# Single_Turnoutv0_2.net
KiCad netlist of a schematic drawn in EAGLE
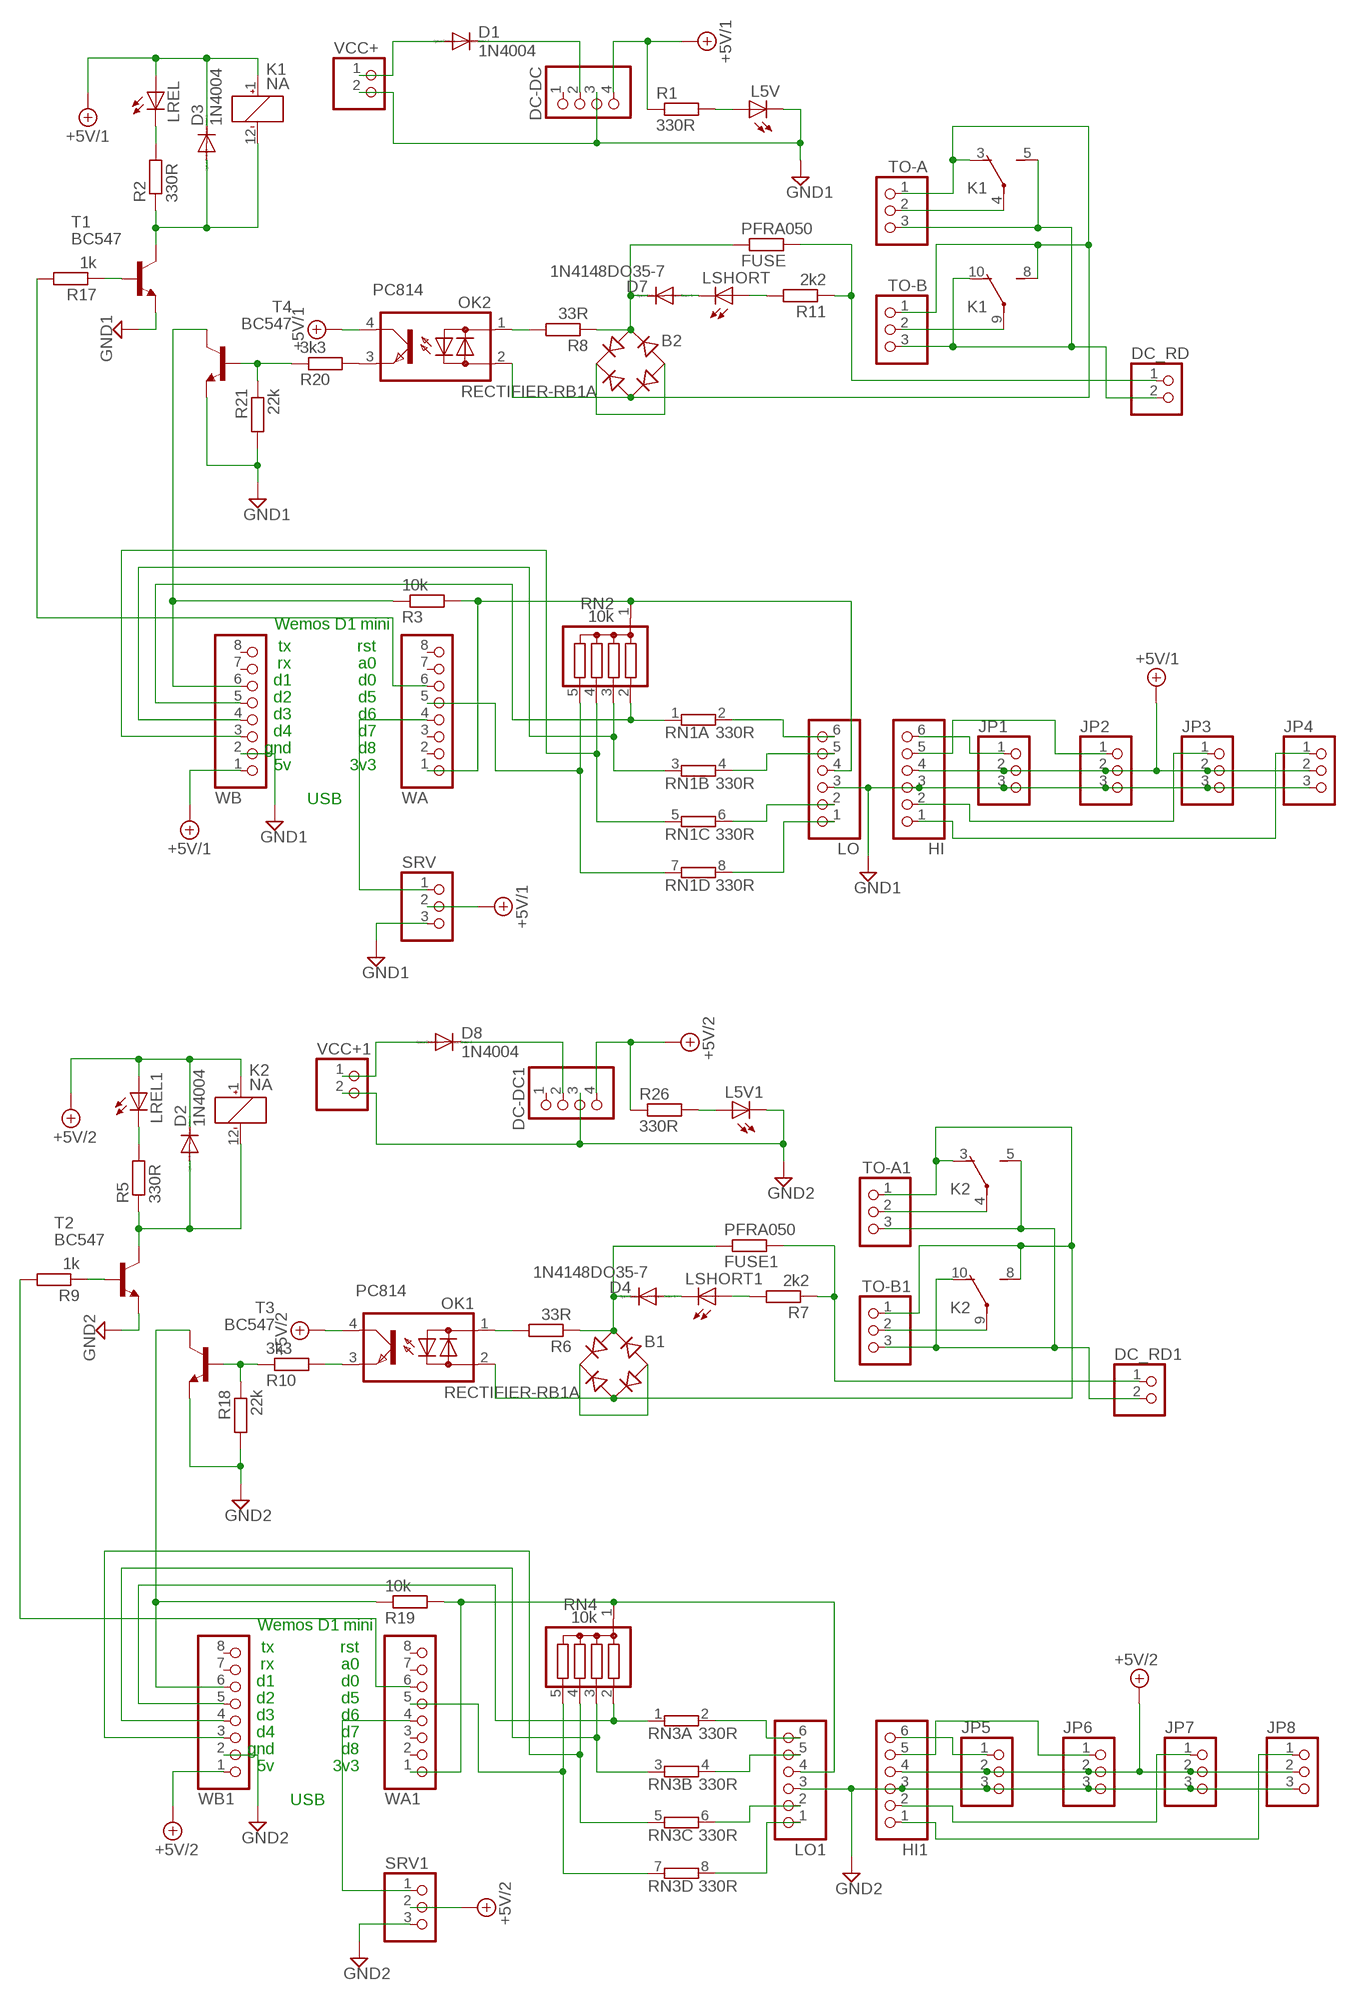
[diagram p0: schematic, sheet 1]

(export (version "E")
  (design (tool "Eeschema 10.0.6"))
  (components
    (comp (ref "B1")
      (value "RECTIFIER-RB1A")
      (footprint "eagle-import:RB1A")
      (libsource (lib "eagle-import") (part "RECTIFIER-RB1A"))
    )
    (comp (ref "B2")
      (value "RECTIFIER-RB1A")
      (footprint "eagle-import:RB1A")
      (libsource (lib "eagle-import") (part "RECTIFIER-RB1A"))
    )
    (comp (ref "D1")
      (value "1N4004")
      (footprint "eagle-import:DO41-10")
      (libsource (lib "eagle-import") (part "1N4004"))
    )
    (comp (ref "D2")
      (value "1N4004")
      (footprint "eagle-import:DO41-10")
      (libsource (lib "eagle-import") (part "1N4004"))
    )
    (comp (ref "D3")
      (value "1N4004")
      (footprint "eagle-import:DO41-10")
      (libsource (lib "eagle-import") (part "1N4004"))
    )
    (comp (ref "D4")
      (value "1N4148DO35-7")
      (footprint "eagle-import:DO35-7")
      (libsource (lib "eagle-import") (part "1N4148DO35-7"))
    )
    (comp (ref "D7")
      (value "1N4148DO35-7")
      (footprint "eagle-import:DO35-7")
      (libsource (lib "eagle-import") (part "1N4148DO35-7"))
    )
    (comp (ref "D8")
      (value "1N4004")
      (footprint "eagle-import:DO41-10")
      (libsource (lib "eagle-import") (part "1N4004"))
    )
    (comp (ref "DC-DC")
      (value "PINHD-1X4")
      (footprint "eagle-import:1X04")
      (libsource (lib "eagle-import") (part "PINHD-1X4"))
    )
    (comp (ref "DC-DC1")
      (value "PINHD-1X4")
      (footprint "eagle-import:1X04")
      (libsource (lib "eagle-import") (part "PINHD-1X4"))
    )
    (comp (ref "DC_RD")
      (value "PINHD-1X2")
      (footprint "eagle-import:1X02")
      (libsource (lib "eagle-import") (part "PINHD-1X2"))
    )
    (comp (ref "DC_RD1")
      (value "PINHD-1X2")
      (footprint "eagle-import:1X02")
      (libsource (lib "eagle-import") (part "PINHD-1X2"))
    )
    (comp (ref "FUSE")
      (value "PFRA050")
      (footprint "eagle-import:0414V")
      (libsource (lib "eagle-import") (part "R-EU_0414/5V"))
    )
    (comp (ref "FUSE1")
      (value "PFRA050")
      (footprint "eagle-import:0414V")
      (libsource (lib "eagle-import") (part "R-EU_0414/5V"))
    )
    (comp (ref "HI")
      (value "PINHD-1X6")
      (footprint "eagle-import:1X06")
      (libsource (lib "eagle-import") (part "PINHD-1X6"))
    )
    (comp (ref "HI1")
      (value "PINHD-1X6")
      (footprint "eagle-import:1X06")
      (libsource (lib "eagle-import") (part "PINHD-1X6"))
    )
    (comp (ref "JP1")
      (value "PINHD-1X3")
      (footprint "eagle-import:1X03")
      (libsource (lib "eagle-import") (part "pinhead_325_PINHD-1X3"))
    )
    (comp (ref "JP2")
      (value "PINHD-1X3")
      (footprint "eagle-import:1X03")
      (libsource (lib "eagle-import") (part "pinhead_325_PINHD-1X3"))
    )
    (comp (ref "JP3")
      (value "PINHD-1X3")
      (footprint "eagle-import:1X03")
      (libsource (lib "eagle-import") (part "pinhead_325_PINHD-1X3"))
    )
    (comp (ref "JP4")
      (value "PINHD-1X3")
      (footprint "eagle-import:1X03")
      (libsource (lib "eagle-import") (part "pinhead_325_PINHD-1X3"))
    )
    (comp (ref "JP5")
      (value "PINHD-1X3")
      (footprint "eagle-import:1X03")
      (libsource (lib "eagle-import") (part "pinhead_325_PINHD-1X3"))
    )
    (comp (ref "JP6")
      (value "PINHD-1X3")
      (footprint "eagle-import:1X03")
      (libsource (lib "eagle-import") (part "pinhead_325_PINHD-1X3"))
    )
    (comp (ref "JP7")
      (value "PINHD-1X3")
      (footprint "eagle-import:1X03")
      (libsource (lib "eagle-import") (part "pinhead_325_PINHD-1X3"))
    )
    (comp (ref "JP8")
      (value "PINHD-1X3")
      (footprint "eagle-import:1X03")
      (libsource (lib "eagle-import") (part "pinhead_325_PINHD-1X3"))
    )
    (comp (ref "K1") (value "NA") (footprint "eagle-import:NA") (libsource (lib "eagle-import") (part "NA")))
    (comp (ref "K2") (value "NA") (footprint "eagle-import:NA") (libsource (lib "eagle-import") (part "NA")))
    (comp (ref "L5V")
      (value "LED3MM")
      (footprint "eagle-import:LED3MM")
      (libsource (lib "eagle-import") (part "LED3MM"))
    )
    (comp (ref "L5V1")
      (value "LED3MM")
      (footprint "eagle-import:LED3MM")
      (libsource (lib "eagle-import") (part "LED3MM"))
    )
    (comp (ref "LO")
      (value "PINHD-1X6")
      (footprint "eagle-import:1X06")
      (libsource (lib "eagle-import") (part "PINHD-1X6"))
    )
    (comp (ref "LO1")
      (value "PINHD-1X6")
      (footprint "eagle-import:1X06")
      (libsource (lib "eagle-import") (part "PINHD-1X6"))
    )
    (comp (ref "LREL")
      (value "LED3MM")
      (footprint "eagle-import:LED3MM")
      (libsource (lib "eagle-import") (part "LED3MM"))
    )
    (comp (ref "LREL1")
      (value "LED3MM")
      (footprint "eagle-import:LED3MM")
      (libsource (lib "eagle-import") (part "LED3MM"))
    )
    (comp (ref "LSHORT")
      (value "LED3MM")
      (footprint "eagle-import:LED3MM")
      (libsource (lib "eagle-import") (part "LED3MM"))
    )
    (comp (ref "LSHORT1")
      (value "LED3MM")
      (footprint "eagle-import:LED3MM")
      (libsource (lib "eagle-import") (part "LED3MM"))
    )
    (comp (ref "OK1")
      (value "PC814")
      (footprint "eagle-import:DIL04")
      (libsource (lib "eagle-import") (part "PC814"))
    )
    (comp (ref "OK2")
      (value "PC814")
      (footprint "eagle-import:DIL04")
      (libsource (lib "eagle-import") (part "PC814"))
    )
    (comp (ref "R1")
      (value "330R")
      (footprint "eagle-import:0207_7")
      (libsource (lib "eagle-import") (part "resistor_348_R-EU_0207/7"))
    )
    (comp (ref "R2")
      (value "330R")
      (footprint "eagle-import:0207_7")
      (libsource (lib "eagle-import") (part "resistor_348_R-EU_0207/7"))
    )
    (comp (ref "R3")
      (value "10k")
      (footprint "eagle-import:0207_7")
      (libsource (lib "eagle-import") (part "resistor_348_R-EU_0207/7"))
    )
    (comp (ref "R5")
      (value "330R")
      (footprint "eagle-import:0207_7")
      (libsource (lib "eagle-import") (part "resistor_348_R-EU_0207/7"))
    )
    (comp (ref "R6")
      (value "33R")
      (footprint "eagle-import:0207_7")
      (libsource (lib "eagle-import") (part "resistor_348_R-EU_0207/7"))
    )
    (comp (ref "R7")
      (value "2k2")
      (footprint "eagle-import:0207_7")
      (libsource (lib "eagle-import") (part "resistor_348_R-EU_0207/7"))
    )
    (comp (ref "R8")
      (value "33R")
      (footprint "eagle-import:0207_7")
      (libsource (lib "eagle-import") (part "resistor_348_R-EU_0207/7"))
    )
    (comp (ref "R9")
      (value "1k")
      (footprint "eagle-import:0207_7")
      (libsource (lib "eagle-import") (part "resistor_348_R-EU_0207/7"))
    )
    (comp (ref "R10")
      (value "3k3")
      (footprint "eagle-import:0207_7")
      (libsource (lib "eagle-import") (part "resistor_348_R-EU_0207/7"))
    )
    (comp (ref "R11")
      (value "2k2")
      (footprint "eagle-import:0207_7")
      (libsource (lib "eagle-import") (part "resistor_348_R-EU_0207/7"))
    )
    (comp (ref "R17")
      (value "1k")
      (footprint "eagle-import:0207_7")
      (libsource (lib "eagle-import") (part "resistor_348_R-EU_0207/7"))
    )
    (comp (ref "R18")
      (value "22k")
      (footprint "eagle-import:0207_7")
      (libsource (lib "eagle-import") (part "resistor_348_R-EU_0207/7"))
    )
    (comp (ref "R19")
      (value "10k")
      (footprint "eagle-import:0207_7")
      (libsource (lib "eagle-import") (part "resistor_348_R-EU_0207/7"))
    )
    (comp (ref "R20")
      (value "3k3")
      (footprint "eagle-import:0207_7")
      (libsource (lib "eagle-import") (part "resistor_348_R-EU_0207/7"))
    )
    (comp (ref "R21")
      (value "22k")
      (footprint "eagle-import:0207_7")
      (libsource (lib "eagle-import") (part "resistor_348_R-EU_0207/7"))
    )
    (comp (ref "R26")
      (value "330R")
      (footprint "eagle-import:0207_7")
      (libsource (lib "eagle-import") (part "resistor_348_R-EU_0207/7"))
    )
    (comp (ref "RN1")
      (value "330R")
      (footprint "eagle-import:SIL8")
      (libsource (lib "eagle-import") (part "E4R"))
    )
    (comp (ref "RN2")
      (value "10k")
      (footprint "eagle-import:SIL5")
      (libsource (lib "eagle-import") (part "G04R"))
    )
    (comp (ref "RN3")
      (value "330R")
      (footprint "eagle-import:SIL8")
      (libsource (lib "eagle-import") (part "E4R"))
    )
    (comp (ref "RN4")
      (value "10k")
      (footprint "eagle-import:SIL5")
      (libsource (lib "eagle-import") (part "G04R"))
    )
    (comp (ref "SRV")
      (value "PINHD-1X3")
      (footprint "eagle-import:1X03")
      (libsource (lib "eagle-import") (part "PINHD-1X3"))
    )
    (comp (ref "SRV1")
      (value "PINHD-1X3")
      (footprint "eagle-import:1X03")
      (libsource (lib "eagle-import") (part "PINHD-1X3"))
    )
    (comp (ref "T1")
      (value "BC547")
      (footprint "eagle-import:TO92")
      (libsource (lib "eagle-import") (part "BC547"))
    )
    (comp (ref "T2")
      (value "BC547")
      (footprint "eagle-import:TO92")
      (libsource (lib "eagle-import") (part "BC547"))
    )
    (comp (ref "T3")
      (value "BC547")
      (footprint "eagle-import:TO92")
      (libsource (lib "eagle-import") (part "BC547"))
    )
    (comp (ref "T4")
      (value "BC547")
      (footprint "eagle-import:TO92")
      (libsource (lib "eagle-import") (part "BC547"))
    )
    (comp (ref "TO-A")
      (value "PINHD-1X3")
      (footprint "eagle-import:1X03")
      (libsource (lib "eagle-import") (part "PINHD-1X3"))
    )
    (comp (ref "TO-A1")
      (value "PINHD-1X3")
      (footprint "eagle-import:1X03")
      (libsource (lib "eagle-import") (part "PINHD-1X3"))
    )
    (comp (ref "TO-B")
      (value "PINHD-1X3")
      (footprint "eagle-import:1X03")
      (libsource (lib "eagle-import") (part "PINHD-1X3"))
    )
    (comp (ref "TO-B1")
      (value "PINHD-1X3")
      (footprint "eagle-import:1X03")
      (libsource (lib "eagle-import") (part "PINHD-1X3"))
    )
    (comp (ref "VCC+")
      (value "PINHD-1X2")
      (footprint "eagle-import:1X02")
      (libsource (lib "eagle-import") (part "PINHD-1X2"))
    )
    (comp (ref "VCC+1")
      (value "PINHD-1X2")
      (footprint "eagle-import:1X02")
      (libsource (lib "eagle-import") (part "PINHD-1X2"))
    )
    (comp (ref "WA")
      (value "PINHD-1X8")
      (footprint "eagle-import:1X08")
      (libsource (lib "eagle-import") (part "PINHD-1X8"))
    )
    (comp (ref "WA1")
      (value "PINHD-1X8")
      (footprint "eagle-import:1X08")
      (libsource (lib "eagle-import") (part "PINHD-1X8"))
    )
    (comp (ref "WB")
      (value "PINHD-1X8")
      (footprint "eagle-import:1X08")
      (libsource (lib "eagle-import") (part "PINHD-1X8"))
    )
    (comp (ref "WB1")
      (value "PINHD-1X8")
      (footprint "eagle-import:1X08")
      (libsource (lib "eagle-import") (part "PINHD-1X8"))
    )
  )
  (nets
    (net (code "1") (name "+5V{slash}1") (class "Default")
      (node (ref "D3") (pin "C") (pinfunction "C_C") (pintype "passive"))
      (node (ref "DC-DC") (pin "4") (pinfunction "4_4") (pintype "passive"))
      (node (ref "HI") (pin "4") (pinfunction "4_4") (pintype "passive"))
      (node (ref "JP1") (pin "2") (pinfunction "2_2") (pintype "passive"))
      (node (ref "JP2") (pin "2") (pinfunction "2_2") (pintype "passive"))
      (node (ref "JP3") (pin "2") (pinfunction "2_2") (pintype "passive"))
      (node (ref "JP4") (pin "2") (pinfunction "2_2") (pintype "passive"))
      (node (ref "K1") (pin "1") (pinfunction "+_1") (pintype "passive"))
      (node (ref "LREL") (pin "A") (pinfunction "A_A") (pintype "passive"))
      (node (ref "OK2") (pin "4") (pinfunction "C_4") (pintype "passive"))
      (node (ref "R1") (pin "1") (pinfunction "1_1") (pintype "passive"))
      (node (ref "SRV") (pin "2") (pinfunction "2_2") (pintype "passive"))
      (node (ref "WB") (pin "1") (pinfunction "1_1") (pintype "passive"))
    )
    (net (code "2") (name "+5V{slash}2") (class "Default")
      (node (ref "D2") (pin "C") (pinfunction "C_C") (pintype "passive"))
      (node (ref "DC-DC1") (pin "4") (pinfunction "4_4") (pintype "passive"))
      (node (ref "HI1") (pin "4") (pinfunction "4_4") (pintype "passive"))
      (node (ref "JP5") (pin "2") (pinfunction "2_2") (pintype "passive"))
      (node (ref "JP6") (pin "2") (pinfunction "2_2") (pintype "passive"))
      (node (ref "JP7") (pin "2") (pinfunction "2_2") (pintype "passive"))
      (node (ref "JP8") (pin "2") (pinfunction "2_2") (pintype "passive"))
      (node (ref "K2") (pin "1") (pinfunction "+_1") (pintype "passive"))
      (node (ref "LREL1") (pin "A") (pinfunction "A_A") (pintype "passive"))
      (node (ref "OK1") (pin "4") (pinfunction "C_4") (pintype "passive"))
      (node (ref "R26") (pin "1") (pinfunction "1_1") (pintype "passive"))
      (node (ref "SRV1") (pin "2") (pinfunction "2_2") (pintype "passive"))
      (node (ref "WB1") (pin "1") (pinfunction "1_1") (pintype "passive"))
    )
    (net (code "3") (name "GND1") (class "Default")
      (node (ref "DC-DC") (pin "3") (pinfunction "3_3") (pintype "passive"))
      (node (ref "HI") (pin "3") (pinfunction "3_3") (pintype "passive"))
      (node (ref "JP1") (pin "3") (pinfunction "3_3") (pintype "passive"))
      (node (ref "JP2") (pin "3") (pinfunction "3_3") (pintype "passive"))
      (node (ref "JP3") (pin "3") (pinfunction "3_3") (pintype "passive"))
      (node (ref "JP4") (pin "3") (pinfunction "3_3") (pintype "passive"))
      (node (ref "L5V") (pin "K") (pinfunction "C_K") (pintype "passive"))
      (node (ref "LO") (pin "3") (pinfunction "3_3") (pintype "passive"))
      (node (ref "R21") (pin "2") (pinfunction "2_2") (pintype "passive"))
      (node (ref "SRV") (pin "3") (pinfunction "3_3") (pintype "passive"))
      (node (ref "T1") (pin "1") (pinfunction "E_1") (pintype "passive"))
      (node (ref "T4") (pin "1") (pinfunction "E_1") (pintype "passive"))
      (node (ref "VCC+") (pin "2") (pinfunction "2_2") (pintype "passive"))
      (node (ref "WB") (pin "2") (pinfunction "2_2") (pintype "passive"))
    )
    (net (code "4") (name "GND2") (class "Default")
      (node (ref "DC-DC1") (pin "3") (pinfunction "3_3") (pintype "passive"))
      (node (ref "HI1") (pin "3") (pinfunction "3_3") (pintype "passive"))
      (node (ref "JP5") (pin "3") (pinfunction "3_3") (pintype "passive"))
      (node (ref "JP6") (pin "3") (pinfunction "3_3") (pintype "passive"))
      (node (ref "JP7") (pin "3") (pinfunction "3_3") (pintype "passive"))
      (node (ref "JP8") (pin "3") (pinfunction "3_3") (pintype "passive"))
      (node (ref "L5V1") (pin "K") (pinfunction "C_K") (pintype "passive"))
      (node (ref "LO1") (pin "3") (pinfunction "3_3") (pintype "passive"))
      (node (ref "R18") (pin "2") (pinfunction "2_2") (pintype "passive"))
      (node (ref "SRV1") (pin "3") (pinfunction "3_3") (pintype "passive"))
      (node (ref "T2") (pin "1") (pinfunction "E_1") (pintype "passive"))
      (node (ref "T3") (pin "1") (pinfunction "E_1") (pintype "passive"))
      (node (ref "VCC+1") (pin "2") (pinfunction "2_2") (pintype "passive"))
      (node (ref "WB1") (pin "2") (pinfunction "2_2") (pintype "passive"))
    )
    (net (code "5") (name "Net-(B1-Pad+)") (class "Default")
      (node (ref "B1") (pin "+") (pinfunction "+_+") (pintype "passive"))
      (node (ref "B1") (pin "-") (pinfunction "-_-") (pintype "passive"))
    )
    (net (code "6") (name "Net-(B1-PadAC1)") (class "Default")
      (node (ref "B1") (pin "AC1") (pinfunction "AC1_AC1") (pintype "passive"))
      (node (ref "D4") (pin "C") (pinfunction "C_C") (pintype "passive"))
      (node (ref "FUSE1") (pin "1") (pinfunction "1_1") (pintype "passive"))
      (node (ref "R6") (pin "1") (pinfunction "1_1") (pintype "passive"))
    )
    (net (code "7") (name "Net-(B2-Pad+)") (class "Default")
      (node (ref "B2") (pin "+") (pinfunction "+_+") (pintype "passive"))
      (node (ref "B2") (pin "-") (pinfunction "-_-") (pintype "passive"))
    )
    (net (code "8") (name "Net-(B2-PadAC1)") (class "Default")
      (node (ref "B2") (pin "AC1") (pinfunction "AC1_AC1") (pintype "passive"))
      (node (ref "D7") (pin "C") (pinfunction "C_C") (pintype "passive"))
      (node (ref "FUSE") (pin "1") (pinfunction "1_1") (pintype "passive"))
      (node (ref "R8") (pin "1") (pinfunction "1_1") (pintype "passive"))
    )
    (net (code "9") (name "Net-(D1-PadA)") (class "Default")
      (node (ref "D1") (pin "A") (pinfunction "A_A") (pintype "passive"))
      (node (ref "VCC+") (pin "1") (pinfunction "1_1") (pintype "passive"))
    )
    (net (code "10") (name "Net-(D1-PadC)") (class "Default")
      (node (ref "D1") (pin "C") (pinfunction "C_C") (pintype "passive"))
      (node (ref "DC-DC") (pin "2") (pinfunction "2_2") (pintype "passive"))
    )
    (net (code "11") (name "Net-(D8-PadA)") (class "Default")
      (node (ref "D8") (pin "A") (pinfunction "A_A") (pintype "passive"))
      (node (ref "VCC+1") (pin "1") (pinfunction "1_1") (pintype "passive"))
    )
    (net (code "12") (name "Net-(D8-PadC)") (class "Default")
      (node (ref "D8") (pin "C") (pinfunction "C_C") (pintype "passive"))
      (node (ref "DC-DC1") (pin "2") (pinfunction "2_2") (pintype "passive"))
    )
    (net (code "13") (name "Net-(DC_RD-Pad1)") (class "Default")
      (node (ref "DC_RD") (pin "1") (pinfunction "1_1") (pintype "passive"))
      (node (ref "FUSE") (pin "2") (pinfunction "2_2") (pintype "passive"))
      (node (ref "R11") (pin "1") (pinfunction "1_1") (pintype "passive"))
    )
    (net (code "14") (name "Net-(DC_RD1-Pad1)") (class "Default")
      (node (ref "DC_RD1") (pin "1") (pinfunction "1_1") (pintype "passive"))
      (node (ref "FUSE1") (pin "2") (pinfunction "2_2") (pintype "passive"))
      (node (ref "R7") (pin "1") (pinfunction "1_1") (pintype "passive"))
    )
    (net (code "15") (name "Net-(HI-Pad1)") (class "Default")
      (node (ref "HI") (pin "1") (pinfunction "1_1") (pintype "passive"))
      (node (ref "JP4") (pin "1") (pinfunction "1_1") (pintype "passive"))
    )
    (net (code "16") (name "Net-(HI-Pad2)") (class "Default")
      (node (ref "HI") (pin "2") (pinfunction "2_2") (pintype "passive"))
      (node (ref "JP3") (pin "1") (pinfunction "1_1") (pintype "passive"))
    )
    (net (code "17") (name "Net-(HI-Pad5)") (class "Default")
      (node (ref "HI") (pin "5") (pinfunction "5_5") (pintype "passive"))
      (node (ref "JP2") (pin "1") (pinfunction "1_1") (pintype "passive"))
    )
    (net (code "18") (name "Net-(HI-Pad6)") (class "Default")
      (node (ref "HI") (pin "6") (pinfunction "6_6") (pintype "passive"))
      (node (ref "JP1") (pin "1") (pinfunction "1_1") (pintype "passive"))
    )
    (net (code "19") (name "Net-(HI1-Pad1)") (class "Default")
      (node (ref "HI1") (pin "1") (pinfunction "1_1") (pintype "passive"))
      (node (ref "JP8") (pin "1") (pinfunction "1_1") (pintype "passive"))
    )
    (net (code "20") (name "Net-(HI1-Pad2)") (class "Default")
      (node (ref "HI1") (pin "2") (pinfunction "2_2") (pintype "passive"))
      (node (ref "JP7") (pin "1") (pinfunction "1_1") (pintype "passive"))
    )
    (net (code "21") (name "Net-(HI1-Pad5)") (class "Default")
      (node (ref "HI1") (pin "5") (pinfunction "5_5") (pintype "passive"))
      (node (ref "JP6") (pin "1") (pinfunction "1_1") (pintype "passive"))
    )
    (net (code "22") (name "Net-(HI1-Pad6)") (class "Default")
      (node (ref "HI1") (pin "6") (pinfunction "6_6") (pintype "passive"))
      (node (ref "JP5") (pin "1") (pinfunction "1_1") (pintype "passive"))
    )
    (net (code "23") (name "Net-(K1A--)") (class "Default")
      (node (ref "D3") (pin "A") (pinfunction "A_A") (pintype "passive"))
      (node (ref "K1") (pin "12") (pinfunction "-_12") (pintype "passive"))
      (node (ref "R2") (pin "1") (pinfunction "1_1") (pintype "passive"))
      (node (ref "T1") (pin "3") (pinfunction "C_3") (pintype "passive"))
    )
    (net (code "24") (name "Net-(K1B-O)") (class "Default")
      (node (ref "B2") (pin "AC2") (pinfunction "AC2_AC2") (pintype "passive"))
      (node (ref "K1") (pin "3") (pinfunction "O_3") (pintype "passive"))
      (node (ref "K1") (pin "8") (pinfunction "S_8") (pintype "passive"))
      (node (ref "OK2") (pin "2") (pinfunction "AC2_2") (pintype "passive"))
      (node (ref "TO-A") (pin "1") (pinfunction "1_1") (pintype "passive"))
      (node (ref "TO-B") (pin "1") (pinfunction "1_1") (pintype "passive"))
    )
    (net (code "25") (name "Net-(K1B-P)") (class "Default")
      (node (ref "K1") (pin "4") (pinfunction "P_4") (pintype "passive"))
      (node (ref "TO-A") (pin "2") (pinfunction "2_2") (pintype "passive"))
    )
    (net (code "26") (name "Net-(K1B-S)") (class "Default")
      (node (ref "DC_RD") (pin "2") (pinfunction "2_2") (pintype "passive"))
      (node (ref "K1") (pin "10") (pinfunction "O_10") (pintype "passive"))
      (node (ref "K1") (pin "5") (pinfunction "S_5") (pintype "passive"))
      (node (ref "TO-A") (pin "3") (pinfunction "3_3") (pintype "passive"))
      (node (ref "TO-B") (pin "3") (pinfunction "3_3") (pintype "passive"))
    )
    (net (code "27") (name "Net-(K1C-P)") (class "Default")
      (node (ref "K1") (pin "9") (pinfunction "P_9") (pintype "passive"))
      (node (ref "TO-B") (pin "2") (pinfunction "2_2") (pintype "passive"))
    )
    (net (code "28") (name "Net-(K2A--)") (class "Default")
      (node (ref "D2") (pin "A") (pinfunction "A_A") (pintype "passive"))
      (node (ref "K2") (pin "12") (pinfunction "-_12") (pintype "passive"))
      (node (ref "R5") (pin "1") (pinfunction "1_1") (pintype "passive"))
      (node (ref "T2") (pin "3") (pinfunction "C_3") (pintype "passive"))
    )
    (net (code "29") (name "Net-(K2B-O)") (class "Default")
      (node (ref "B1") (pin "AC2") (pinfunction "AC2_AC2") (pintype "passive"))
      (node (ref "K2") (pin "3") (pinfunction "O_3") (pintype "passive"))
      (node (ref "K2") (pin "8") (pinfunction "S_8") (pintype "passive"))
      (node (ref "OK1") (pin "2") (pinfunction "AC2_2") (pintype "passive"))
      (node (ref "TO-A1") (pin "1") (pinfunction "1_1") (pintype "passive"))
      (node (ref "TO-B1") (pin "1") (pinfunction "1_1") (pintype "passive"))
    )
    (net (code "30") (name "Net-(K2B-P)") (class "Default")
      (node (ref "K2") (pin "4") (pinfunction "P_4") (pintype "passive"))
      (node (ref "TO-A1") (pin "2") (pinfunction "2_2") (pintype "passive"))
    )
    (net (code "31") (name "Net-(K2B-S)") (class "Default")
      (node (ref "DC_RD1") (pin "2") (pinfunction "2_2") (pintype "passive"))
      (node (ref "K2") (pin "10") (pinfunction "O_10") (pintype "passive"))
      (node (ref "K2") (pin "5") (pinfunction "S_5") (pintype "passive"))
      (node (ref "TO-A1") (pin "3") (pinfunction "3_3") (pintype "passive"))
      (node (ref "TO-B1") (pin "3") (pinfunction "3_3") (pintype "passive"))
    )
    (net (code "32") (name "Net-(K2C-P)") (class "Default")
      (node (ref "K2") (pin "9") (pinfunction "P_9") (pintype "passive"))
      (node (ref "TO-B1") (pin "2") (pinfunction "2_2") (pintype "passive"))
    )
    (net (code "33") (name "Net-(L5V-PadA)") (class "Default")
      (node (ref "L5V") (pin "A") (pinfunction "A_A") (pintype "passive"))
      (node (ref "R1") (pin "2") (pinfunction "2_2") (pintype "passive"))
    )
    (net (code "34") (name "Net-(L5V1-PadA)") (class "Default")
      (node (ref "L5V1") (pin "A") (pinfunction "A_A") (pintype "passive"))
      (node (ref "R26") (pin "2") (pinfunction "2_2") (pintype "passive"))
    )
    (net (code "35") (name "Net-(LO-Pad4)") (class "Default")
      (node (ref "LO") (pin "4") (pinfunction "4_4") (pintype "passive"))
      (node (ref "R3") (pin "2") (pinfunction "2_2") (pintype "passive"))
      (node (ref "RN2") (pin "1") (pinfunction "1_1") (pintype "passive"))
      (node (ref "WA") (pin "1") (pinfunction "1_1") (pintype "passive"))
    )
    (net (code "36") (name "Net-(LO-Pad6)") (class "Default")
      (node (ref "LO") (pin "6") (pinfunction "6_6") (pintype "passive"))
      (node (ref "RN1") (pin "2") (pinfunction "2_2") (pintype "passive"))
    )
    (net (code "37") (name "Net-(LO1-Pad4)") (class "Default")
      (node (ref "LO1") (pin "4") (pinfunction "4_4") (pintype "passive"))
      (node (ref "R19") (pin "2") (pinfunction "2_2") (pintype "passive"))
      (node (ref "RN4") (pin "1") (pinfunction "1_1") (pintype "passive"))
      (node (ref "WA1") (pin "1") (pinfunction "1_1") (pintype "passive"))
    )
    (net (code "38") (name "Net-(LO1-Pad6)") (class "Default")
      (node (ref "LO1") (pin "6") (pinfunction "6_6") (pintype "passive"))
      (node (ref "RN3") (pin "2") (pinfunction "2_2") (pintype "passive"))
    )
    (net (code "39") (name "Net-(LREL-C)") (class "Default")
      (node (ref "LREL") (pin "K") (pinfunction "C_K") (pintype "passive"))
      (node (ref "R2") (pin "2") (pinfunction "2_2") (pintype "passive"))
    )
    (net (code "40") (name "Net-(LREL1-C)") (class "Default")
      (node (ref "LREL1") (pin "K") (pinfunction "C_K") (pintype "passive"))
      (node (ref "R5") (pin "2") (pinfunction "2_2") (pintype "passive"))
    )
    (net (code "41") (name "Net-(LSHORT-C)") (class "Default")
      (node (ref "D7") (pin "A") (pinfunction "A_A") (pintype "passive"))
      (node (ref "LSHORT") (pin "K") (pinfunction "C_K") (pintype "passive"))
    )
    (net (code "42") (name "Net-(LSHORT-PadA)") (class "Default")
      (node (ref "LSHORT") (pin "A") (pinfunction "A_A") (pintype "passive"))
      (node (ref "R11") (pin "2") (pinfunction "2_2") (pintype "passive"))
    )
    (net (code "43") (name "Net-(LSHORT1-C)") (class "Default")
      (node (ref "D4") (pin "A") (pinfunction "A_A") (pintype "passive"))
      (node (ref "LSHORT1") (pin "K") (pinfunction "C_K") (pintype "passive"))
    )
    (net (code "44") (name "Net-(LSHORT1-PadA)") (class "Default")
      (node (ref "LSHORT1") (pin "A") (pinfunction "A_A") (pintype "passive"))
      (node (ref "R7") (pin "2") (pinfunction "2_2") (pintype "passive"))
    )
    (net (code "45") (name "Net-(OK1-AC1)") (class "Default")
      (node (ref "OK1") (pin "1") (pinfunction "AC1_1") (pintype "passive"))
      (node (ref "R6") (pin "2") (pinfunction "2_2") (pintype "passive"))
    )
    (net (code "46") (name "Net-(OK1-E)") (class "Default")
      (node (ref "OK1") (pin "3") (pinfunction "E_3") (pintype "passive"))
      (node (ref "R10") (pin "2") (pinfunction "2_2") (pintype "passive"))
    )
    (net (code "47") (name "Net-(OK2-AC1)") (class "Default")
      (node (ref "OK2") (pin "1") (pinfunction "AC1_1") (pintype "passive"))
      (node (ref "R8") (pin "2") (pinfunction "2_2") (pintype "passive"))
    )
    (net (code "48") (name "Net-(OK2-E)") (class "Default")
      (node (ref "OK2") (pin "3") (pinfunction "E_3") (pintype "passive"))
      (node (ref "R20") (pin "2") (pinfunction "2_2") (pintype "passive"))
    )
    (net (code "49") (name "Net-(R9-Pad2)") (class "Default")
      (node (ref "R9") (pin "2") (pinfunction "2_2") (pintype "passive"))
      (node (ref "WA1") (pin "6") (pinfunction "6_6") (pintype "passive"))
    )
    (net (code "50") (name "Net-(R17-Pad2)") (class "Default")
      (node (ref "R17") (pin "2") (pinfunction "2_2") (pintype "passive"))
      (node (ref "WA") (pin "6") (pinfunction "6_6") (pintype "passive"))
    )
    (net (code "51") (name "Net-(RN1-Pad1)") (class "Default")
      (node (ref "RN1") (pin "1") (pinfunction "1_1") (pintype "passive"))
      (node (ref "RN2") (pin "2") (pinfunction "2_2") (pintype "passive"))
      (node (ref "WB") (pin "5") (pinfunction "5_5") (pintype "passive"))
    )
    (net (code "52") (name "Net-(RN1B-1)") (class "Default")
      (node (ref "RN1") (pin "3") (pinfunction "1_3") (pintype "passive"))
      (node (ref "RN2") (pin "3") (pinfunction "3_3") (pintype "passive"))
      (node (ref "WB") (pin "4") (pinfunction "4_4") (pintype "passive"))
    )
    (net (code "53") (name "Net-(RN1B-2)") (class "Default")
      (node (ref "LO") (pin "5") (pinfunction "5_5") (pintype "passive"))
      (node (ref "RN1") (pin "4") (pinfunction "2_4") (pintype "passive"))
    )
    (net (code "54") (name "Net-(RN1C-1)") (class "Default")
      (node (ref "RN1") (pin "5") (pinfunction "1_5") (pintype "passive"))
      (node (ref "RN2") (pin "4") (pinfunction "4_4") (pintype "passive"))
      (node (ref "WB") (pin "3") (pinfunction "3_3") (pintype "passive"))
    )
    (net (code "55") (name "Net-(RN1C-2)") (class "Default")
      (node (ref "LO") (pin "2") (pinfunction "2_2") (pintype "passive"))
      (node (ref "RN1") (pin "6") (pinfunction "2_6") (pintype "passive"))
    )
    (net (code "56") (name "Net-(RN1D-1)") (class "Default")
      (node (ref "RN1") (pin "7") (pinfunction "1_7") (pintype "passive"))
      (node (ref "RN2") (pin "5") (pinfunction "5_5") (pintype "passive"))
      (node (ref "WA") (pin "5") (pinfunction "5_5") (pintype "passive"))
    )
    (net (code "57") (name "Net-(RN1D-2)") (class "Default")
      (node (ref "LO") (pin "1") (pinfunction "1_1") (pintype "passive"))
      (node (ref "RN1") (pin "8") (pinfunction "2_8") (pintype "passive"))
    )
    (net (code "58") (name "Net-(RN3-Pad1)") (class "Default")
      (node (ref "RN3") (pin "1") (pinfunction "1_1") (pintype "passive"))
      (node (ref "RN4") (pin "2") (pinfunction "2_2") (pintype "passive"))
      (node (ref "WB1") (pin "5") (pinfunction "5_5") (pintype "passive"))
    )
    (net (code "59") (name "Net-(RN3B-1)") (class "Default")
      (node (ref "RN3") (pin "3") (pinfunction "1_3") (pintype "passive"))
      (node (ref "RN4") (pin "3") (pinfunction "3_3") (pintype "passive"))
      (node (ref "WB1") (pin "4") (pinfunction "4_4") (pintype "passive"))
    )
    (net (code "60") (name "Net-(RN3B-2)") (class "Default")
      (node (ref "LO1") (pin "5") (pinfunction "5_5") (pintype "passive"))
      (node (ref "RN3") (pin "4") (pinfunction "2_4") (pintype "passive"))
    )
    (net (code "61") (name "Net-(RN3C-1)") (class "Default")
      (node (ref "RN3") (pin "5") (pinfunction "1_5") (pintype "passive"))
      (node (ref "RN4") (pin "4") (pinfunction "4_4") (pintype "passive"))
      (node (ref "WB1") (pin "3") (pinfunction "3_3") (pintype "passive"))
    )
    (net (code "62") (name "Net-(RN3C-2)") (class "Default")
      (node (ref "LO1") (pin "2") (pinfunction "2_2") (pintype "passive"))
      (node (ref "RN3") (pin "6") (pinfunction "2_6") (pintype "passive"))
    )
    (net (code "63") (name "Net-(RN3D-1)") (class "Default")
      (node (ref "RN3") (pin "7") (pinfunction "1_7") (pintype "passive"))
      (node (ref "RN4") (pin "5") (pinfunction "5_5") (pintype "passive"))
      (node (ref "WA1") (pin "5") (pinfunction "5_5") (pintype "passive"))
    )
    (net (code "64") (name "Net-(RN3D-2)") (class "Default")
      (node (ref "LO1") (pin "1") (pinfunction "1_1") (pintype "passive"))
      (node (ref "RN3") (pin "8") (pinfunction "2_8") (pintype "passive"))
    )
    (net (code "65") (name "Net-(SRV-Pad1)") (class "Default")
      (node (ref "SRV") (pin "1") (pinfunction "1_1") (pintype "passive"))
      (node (ref "WA") (pin "4") (pinfunction "4_4") (pintype "passive"))
    )
    (net (code "66") (name "Net-(SRV1-Pad1)") (class "Default")
      (node (ref "SRV1") (pin "1") (pinfunction "1_1") (pintype "passive"))
      (node (ref "WA1") (pin "4") (pinfunction "4_4") (pintype "passive"))
    )
    (net (code "67") (name "Net-(T1-B)") (class "Default")
      (node (ref "R17") (pin "1") (pinfunction "1_1") (pintype "passive"))
      (node (ref "T1") (pin "2") (pinfunction "B_2") (pintype "passive"))
    )
    (net (code "68") (name "Net-(T2-B)") (class "Default")
      (node (ref "R9") (pin "1") (pinfunction "1_1") (pintype "passive"))
      (node (ref "T2") (pin "2") (pinfunction "B_2") (pintype "passive"))
    )
    (net (code "69") (name "Net-(T3-B)") (class "Default")
      (node (ref "R10") (pin "1") (pinfunction "1_1") (pintype "passive"))
      (node (ref "R18") (pin "1") (pinfunction "1_1") (pintype "passive"))
      (node (ref "T3") (pin "2") (pinfunction "B_2") (pintype "passive"))
    )
    (net (code "70") (name "Net-(T3-C)") (class "Default")
      (node (ref "R19") (pin "1") (pinfunction "1_1") (pintype "passive"))
      (node (ref "T3") (pin "3") (pinfunction "C_3") (pintype "passive"))
      (node (ref "WB1") (pin "6") (pinfunction "6_6") (pintype "passive"))
    )
    (net (code "71") (name "Net-(T4-B)") (class "Default")
      (node (ref "R20") (pin "1") (pinfunction "1_1") (pintype "passive"))
      (node (ref "R21") (pin "1") (pinfunction "1_1") (pintype "passive"))
      (node (ref "T4") (pin "2") (pinfunction "B_2") (pintype "passive"))
    )
    (net (code "72") (name "Net-(T4-C)") (class "Default")
      (node (ref "R3") (pin "1") (pinfunction "1_1") (pintype "passive"))
      (node (ref "T4") (pin "3") (pinfunction "C_3") (pintype "passive"))
      (node (ref "WB") (pin "6") (pinfunction "6_6") (pintype "passive"))
    )
    (net (code "73") (name "unconnected-(DC-DC-Pad1)") (class "Default")
      (node (ref "DC-DC") (pin "1") (pinfunction "1_1") (pintype "passive"))
    )
    (net (code "74") (name "unconnected-(DC-DC1-Pad1)") (class "Default")
      (node (ref "DC-DC1") (pin "1") (pinfunction "1_1") (pintype "passive"))
    )
    (net (code "75") (name "unconnected-(WA-Pad2)") (class "Default")
      (node (ref "WA") (pin "2") (pinfunction "2_2") (pintype "passive"))
    )
    (net (code "76") (name "unconnected-(WA-Pad3)") (class "Default")
      (node (ref "WA") (pin "3") (pinfunction "3_3") (pintype "passive"))
    )
    (net (code "77") (name "unconnected-(WA-Pad7)") (class "Default")
      (node (ref "WA") (pin "7") (pinfunction "7_7") (pintype "passive"))
    )
    (net (code "78") (name "unconnected-(WA-Pad8)") (class "Default")
      (node (ref "WA") (pin "8") (pinfunction "8_8") (pintype "passive"))
    )
    (net (code "79") (name "unconnected-(WA1-Pad2)") (class "Default")
      (node (ref "WA1") (pin "2") (pinfunction "2_2") (pintype "passive"))
    )
    (net (code "80") (name "unconnected-(WA1-Pad3)") (class "Default")
      (node (ref "WA1") (pin "3") (pinfunction "3_3") (pintype "passive"))
    )
    (net (code "81") (name "unconnected-(WA1-Pad7)") (class "Default")
      (node (ref "WA1") (pin "7") (pinfunction "7_7") (pintype "passive"))
    )
    (net (code "82") (name "unconnected-(WA1-Pad8)") (class "Default")
      (node (ref "WA1") (pin "8") (pinfunction "8_8") (pintype "passive"))
    )
    (net (code "83") (name "unconnected-(WB-Pad7)") (class "Default")
      (node (ref "WB") (pin "7") (pinfunction "7_7") (pintype "passive"))
    )
    (net (code "84") (name "unconnected-(WB-Pad8)") (class "Default")
      (node (ref "WB") (pin "8") (pinfunction "8_8") (pintype "passive"))
    )
    (net (code "85") (name "unconnected-(WB1-Pad7)") (class "Default")
      (node (ref "WB1") (pin "7") (pinfunction "7_7") (pintype "passive"))
    )
    (net (code "86") (name "unconnected-(WB1-Pad8)") (class "Default")
      (node (ref "WB1") (pin "8") (pinfunction "8_8") (pintype "passive"))
    )
  )
)
